# TRV_ANAREN_V0_5.net
KiCad netlist of a schematic drawn in EAGLE
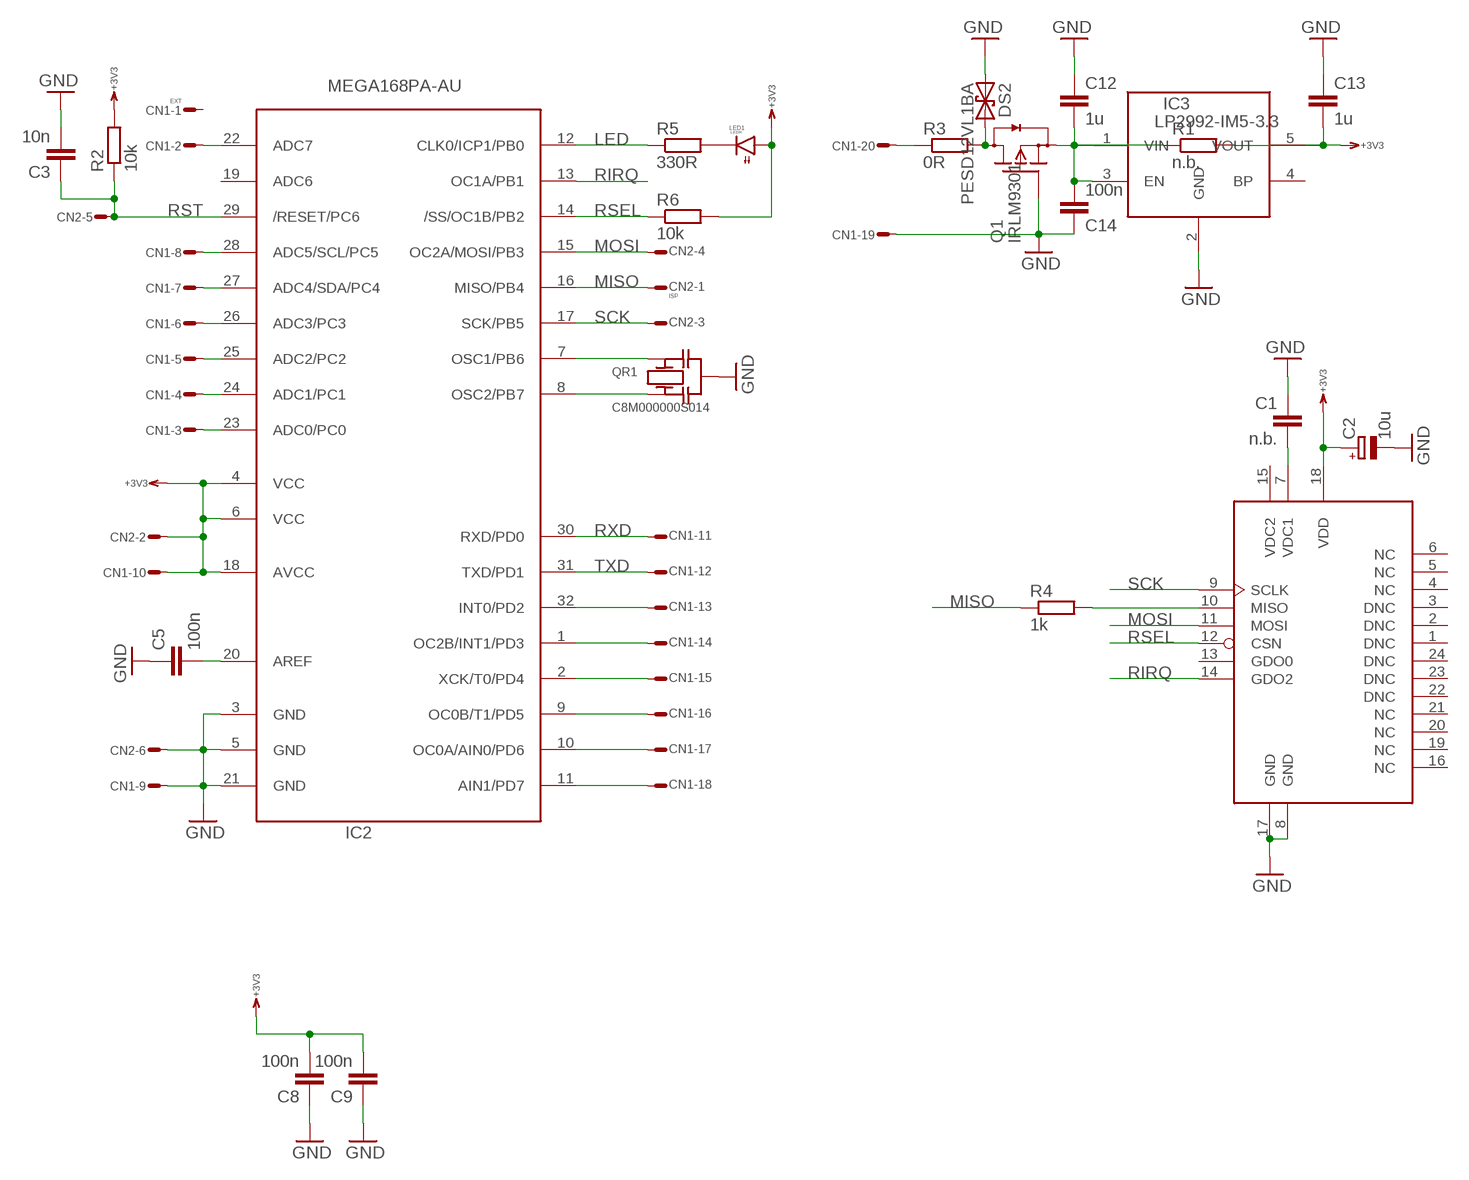
[diagram p0: schematic, sheet 1]

(export (version "E")
  (design (tool "Eeschema 10.0.6"))
  (components
    (comp (ref "C1")
      (value "n.b.")
      (footprint "eagle-import:0603")
      (libsource (lib "eagle-import") (part "C0603"))
    )
    (comp (ref "C2")
      (value "10u")
      (footprint "eagle-import:SMC_B")
      (libsource (lib "eagle-import") (part "C_POLSMCB"))
    )
    (comp (ref "C3")
      (value "10n")
      (footprint "eagle-import:0603")
      (libsource (lib "eagle-import") (part "C0603"))
    )
    (comp (ref "C5")
      (value "100n")
      (footprint "eagle-import:0603")
      (libsource (lib "eagle-import") (part "C0603"))
    )
    (comp (ref "C8")
      (value "100n")
      (footprint "eagle-import:0603")
      (libsource (lib "eagle-import") (part "C0603"))
    )
    (comp (ref "C9")
      (value "100n")
      (footprint "eagle-import:0603")
      (libsource (lib "eagle-import") (part "C0603"))
    )
    (comp (ref "C12")
      (value "1u")
      (footprint "eagle-import:0603")
      (libsource (lib "eagle-import") (part "C0603"))
    )
    (comp (ref "C13")
      (value "1u")
      (footprint "eagle-import:0603")
      (libsource (lib "eagle-import") (part "C0603"))
    )
    (comp (ref "C14")
      (value "100n")
      (footprint "eagle-import:0603")
      (libsource (lib "eagle-import") (part "C0603"))
    )
    (comp (ref "CN1")
      (value "EXT")
      (footprint "eagle-import:ML20S")
      (libsource (lib "eagle-import") (part "ML20?ES"))
    )
    (comp (ref "CN2")
      (value "ISP")
      (footprint "eagle-import:ML6S")
      (libsource (lib "eagle-import") (part "ML6ES"))
    )
    (comp (ref "DS2")
      (value "PESD12VL1BA")
      (footprint "eagle-import:SOD323")
      (libsource (lib "eagle-import") (part "TVS-U323"))
    )
    (comp (ref "IC2")
      (value "MEGA168PA-AU")
      (footprint "eagle-import:TQFP32-08")
      (libsource (lib "eagle-import") (part "MEGA168PA"))
    )
    (comp (ref "IC3")
      (value "LP2992-IM5-3.3")
      (footprint "eagle-import:SOT23-5")
      (libsource (lib "eagle-import") (part "LDO"))
    )
    (comp (ref "LED1")
      (value "LEDR")
      (footprint "eagle-import:0603")
      (libsource (lib "eagle-import") (part "LED0603"))
    )
    (comp (ref "Q1")
      (value "IRLM9301")
      (footprint "eagle-import:SOT23")
      (libsource (lib "eagle-import") (part "FET-PDSOT23"))
    )
    (comp (ref "QR1")
      (value "C8M000000S014")
      (footprint "eagle-import:CR")
      (libsource (lib "eagle-import") (part "QRCR"))
    )
    (comp (ref "R1")
      (value "n.b.")
      (footprint "eagle-import:0603")
      (libsource (lib "eagle-import") (part "R0603"))
    )
    (comp (ref "R2")
      (value "10k")
      (footprint "eagle-import:0603")
      (libsource (lib "eagle-import") (part "R0603"))
    )
    (comp (ref "R3")
      (value "0R")
      (footprint "eagle-import:0603")
      (libsource (lib "eagle-import") (part "R0603"))
    )
    (comp (ref "R4")
      (value "1k")
      (footprint "eagle-import:0603")
      (libsource (lib "eagle-import") (part "R0603"))
    )
    (comp (ref "R5")
      (value "330R")
      (footprint "eagle-import:0603")
      (libsource (lib "eagle-import") (part "R0603"))
    )
    (comp (ref "R6")
      (value "10k")
      (footprint "eagle-import:0603")
      (libsource (lib "eagle-import") (part "R0603"))
    )
    (comp (ref "RF1")
      (value "ANARENC")
      (footprint "eagle-import:ANAREN_C")
      (libsource (lib "eagle-import") (part "ANARENC"))
    )
  )
  (nets
    (net (code "1") (name "+3V3") (class "Default")
      (node (ref "C13") (pin "2") (pinfunction "2_2") (pintype "passive"))
      (node (ref "C2") (pin "+") (pinfunction "+_+") (pintype "passive"))
      (node (ref "C8") (pin "2") (pinfunction "2_2") (pintype "passive"))
      (node (ref "C9") (pin "2") (pinfunction "2_2") (pintype "passive"))
      (node (ref "CN1") (pin "10") (pinfunction "S_10") (pintype "passive"))
      (node (ref "CN2") (pin "2") (pinfunction "S_2") (pintype "passive"))
      (node (ref "IC2") (pin "18") (pinfunction "AVCC_18") (pintype "bidirectional"))
      (node (ref "IC2") (pin "4") (pinfunction "VCC_4") (pintype "bidirectional"))
      (node (ref "IC2") (pin "6") (pinfunction "VCC_6") (pintype "bidirectional"))
      (node (ref "IC3") (pin "5") (pinfunction "VOUT_5") (pintype "bidirectional"))
      (node (ref "LED1") (pin "1") (pinfunction "A_1") (pintype "bidirectional"))
      (node (ref "R1") (pin "2") (pinfunction "2_2") (pintype "passive"))
      (node (ref "R2") (pin "2") (pinfunction "2_2") (pintype "passive"))
      (node (ref "R6") (pin "2") (pinfunction "2_2") (pintype "passive"))
      (node (ref "RF1") (pin "18") (pinfunction "VDD_18") (pintype "bidirectional"))
    )
    (net (code "2") (name "/LED") (class "Default")
      (node (ref "IC2") (pin "12") (pinfunction "CLK0/ICP1/PB0_12") (pintype "bidirectional"))
      (node (ref "R5") (pin "1") (pinfunction "1_1") (pintype "passive"))
    )
    (net (code "3") (name "/MISO") (class "Default")
      (node (ref "CN2") (pin "1") (pinfunction "S_1") (pintype "passive"))
      (node (ref "IC2") (pin "16") (pinfunction "MISO/PB4_16") (pintype "bidirectional"))
      (node (ref "R4") (pin "1") (pinfunction "1_1") (pintype "passive"))
    )
    (net (code "4") (name "/MOSI") (class "Default")
      (node (ref "CN2") (pin "4") (pinfunction "S_4") (pintype "passive"))
      (node (ref "IC2") (pin "15") (pinfunction "OC2A/MOSI/PB3_15") (pintype "bidirectional"))
      (node (ref "RF1") (pin "11") (pinfunction "MOSI_11") (pintype "input"))
    )
    (net (code "5") (name "/RIRQ") (class "Default")
      (node (ref "IC2") (pin "13") (pinfunction "OC1A/PB1_13") (pintype "bidirectional"))
      (node (ref "RF1") (pin "14") (pinfunction "GDO2_14") (pintype "bidirectional"))
    )
    (net (code "6") (name "/RSEL") (class "Default")
      (node (ref "IC2") (pin "14") (pinfunction "/SS/OC1B/PB2_14") (pintype "bidirectional"))
      (node (ref "R6") (pin "1") (pinfunction "1_1") (pintype "passive"))
      (node (ref "RF1") (pin "12") (pinfunction "CSN_12") (pintype "input"))
    )
    (net (code "7") (name "/RST") (class "Default")
      (node (ref "C3") (pin "1") (pinfunction "1_1") (pintype "passive"))
      (node (ref "CN2") (pin "5") (pinfunction "S_5") (pintype "passive"))
      (node (ref "IC2") (pin "29") (pinfunction "/RESET/PC6_29") (pintype "bidirectional"))
      (node (ref "R2") (pin "1") (pinfunction "1_1") (pintype "passive"))
    )
    (net (code "8") (name "/RXD") (class "Default")
      (node (ref "CN1") (pin "11") (pinfunction "S_11") (pintype "passive"))
      (node (ref "IC2") (pin "30") (pinfunction "RXD/PD0_30") (pintype "bidirectional"))
    )
    (net (code "9") (name "/SCK") (class "Default")
      (node (ref "CN2") (pin "3") (pinfunction "S_3") (pintype "passive"))
      (node (ref "IC2") (pin "17") (pinfunction "SCK/PB5_17") (pintype "bidirectional"))
      (node (ref "RF1") (pin "9") (pinfunction "SCLK_9") (pintype "input"))
    )
    (net (code "10") (name "/TXD") (class "Default")
      (node (ref "CN1") (pin "12") (pinfunction "S_12") (pintype "passive"))
      (node (ref "IC2") (pin "31") (pinfunction "TXD/PD1_31") (pintype "bidirectional"))
    )
    (net (code "11") (name "GND") (class "Default")
      (node (ref "C1") (pin "1") (pinfunction "1_1") (pintype "passive"))
      (node (ref "C12") (pin "1") (pinfunction "1_1") (pintype "passive"))
      (node (ref "C13") (pin "1") (pinfunction "1_1") (pintype "passive"))
      (node (ref "C14") (pin "1") (pinfunction "1_1") (pintype "passive"))
      (node (ref "C2") (pin "-") (pinfunction "-_-") (pintype "passive"))
      (node (ref "C3") (pin "2") (pinfunction "2_2") (pintype "passive"))
      (node (ref "C5") (pin "1") (pinfunction "1_1") (pintype "passive"))
      (node (ref "C8") (pin "1") (pinfunction "1_1") (pintype "passive"))
      (node (ref "C9") (pin "1") (pinfunction "1_1") (pintype "passive"))
      (node (ref "CN1") (pin "19") (pinfunction "S_19") (pintype "passive"))
      (node (ref "CN1") (pin "9") (pinfunction "S_9") (pintype "passive"))
      (node (ref "CN2") (pin "6") (pinfunction "S_6") (pintype "passive"))
      (node (ref "DS2") (pin "A") (pinfunction "1_A") (pintype "passive"))
      (node (ref "IC2") (pin "21") (pinfunction "GND_21") (pintype "bidirectional"))
      (node (ref "IC2") (pin "3") (pinfunction "GND_3") (pintype "bidirectional"))
      (node (ref "IC2") (pin "5") (pinfunction "GND_5") (pintype "bidirectional"))
      (node (ref "IC3") (pin "2") (pinfunction "GND_2") (pintype "bidirectional"))
      (node (ref "Q1") (pin "1") (pinfunction "G_1") (pintype "passive"))
      (node (ref "QR1") (pin "M") (pinfunction "M_M") (pintype "passive"))
      (node (ref "RF1") (pin "17") (pinfunction "GND_17") (pintype "bidirectional"))
      (node (ref "RF1") (pin "8") (pinfunction "GND_8") (pintype "bidirectional"))
    )
    (net (code "12") (name "Net-(CN1E-S)") (class "Default")
      (node (ref "CN1") (pin "13") (pinfunction "S_13") (pintype "passive"))
      (node (ref "IC2") (pin "32") (pinfunction "INT0/PD2_32") (pintype "bidirectional"))
    )
    (net (code "13") (name "Net-(CN1F-S)") (class "Default")
      (node (ref "CN1") (pin "14") (pinfunction "S_14") (pintype "passive"))
      (node (ref "IC2") (pin "1") (pinfunction "OC2B/INT1/PD3_1") (pintype "bidirectional"))
    )
    (net (code "14") (name "Net-(CN1G-S)") (class "Default")
      (node (ref "CN1") (pin "15") (pinfunction "S_15") (pintype "passive"))
      (node (ref "IC2") (pin "2") (pinfunction "XCK/T0/PD4_2") (pintype "bidirectional"))
    )
    (net (code "15") (name "Net-(CN1H-S)") (class "Default")
      (node (ref "CN1") (pin "16") (pinfunction "S_16") (pintype "passive"))
      (node (ref "IC2") (pin "9") (pinfunction "OC0B/T1/PD5_9") (pintype "bidirectional"))
    )
    (net (code "16") (name "Net-(CN1I-S)") (class "Default")
      (node (ref "CN1") (pin "17") (pinfunction "S_17") (pintype "passive"))
      (node (ref "IC2") (pin "10") (pinfunction "OC0A/AIN0/PD6_10") (pintype "bidirectional"))
    )
    (net (code "17") (name "Net-(CN1J-S)") (class "Default")
      (node (ref "CN1") (pin "18") (pinfunction "S_18") (pintype "passive"))
      (node (ref "IC2") (pin "11") (pinfunction "AIN1/PD7_11") (pintype "bidirectional"))
    )
    (net (code "18") (name "Net-(CN1L-S)") (class "Default")
      (node (ref "CN1") (pin "2") (pinfunction "S_2") (pintype "passive"))
      (node (ref "IC2") (pin "22") (pinfunction "ADC7_22") (pintype "bidirectional"))
    )
    (net (code "19") (name "Net-(CN1M-S)") (class "Default")
      (node (ref "CN1") (pin "20") (pinfunction "S_20") (pintype "passive"))
      (node (ref "R3") (pin "1") (pinfunction "1_1") (pintype "passive"))
    )
    (net (code "20") (name "Net-(CN1N-S)") (class "Default")
      (node (ref "CN1") (pin "3") (pinfunction "S_3") (pintype "passive"))
      (node (ref "IC2") (pin "23") (pinfunction "ADC0/PC0_23") (pintype "bidirectional"))
    )
    (net (code "21") (name "Net-(CN1O-S)") (class "Default")
      (node (ref "CN1") (pin "4") (pinfunction "S_4") (pintype "passive"))
      (node (ref "IC2") (pin "24") (pinfunction "ADC1/PC1_24") (pintype "bidirectional"))
    )
    (net (code "22") (name "Net-(CN1P-S)") (class "Default")
      (node (ref "CN1") (pin "5") (pinfunction "S_5") (pintype "passive"))
      (node (ref "IC2") (pin "25") (pinfunction "ADC2/PC2_25") (pintype "bidirectional"))
    )
    (net (code "23") (name "Net-(CN1Q-S)") (class "Default")
      (node (ref "CN1") (pin "6") (pinfunction "S_6") (pintype "passive"))
      (node (ref "IC2") (pin "26") (pinfunction "ADC3/PC3_26") (pintype "bidirectional"))
    )
    (net (code "24") (name "Net-(CN1R-S)") (class "Default")
      (node (ref "CN1") (pin "7") (pinfunction "S_7") (pintype "passive"))
      (node (ref "IC2") (pin "27") (pinfunction "ADC4/SDA/PC4_27") (pintype "bidirectional"))
    )
    (net (code "25") (name "Net-(CN1S-S)") (class "Default")
      (node (ref "CN1") (pin "8") (pinfunction "S_8") (pintype "passive"))
      (node (ref "IC2") (pin "28") (pinfunction "ADC5/SCL/PC5_28") (pintype "bidirectional"))
    )
    (net (code "26") (name "Net-(DS2-2)") (class "Default")
      (node (ref "DS2") (pin "C") (pinfunction "2_C") (pintype "passive"))
      (node (ref "Q1") (pin "3") (pinfunction "D_3") (pintype "passive"))
      (node (ref "R3") (pin "2") (pinfunction "2_2") (pintype "passive"))
    )
    (net (code "27") (name "Net-(IC2-AREF)") (class "Default")
      (node (ref "C5") (pin "2") (pinfunction "2_2") (pintype "passive"))
      (node (ref "IC2") (pin "20") (pinfunction "AREF_20") (pintype "bidirectional"))
    )
    (net (code "28") (name "Net-(IC2-OSC1{slash}PB6)") (class "Default")
      (node (ref "IC2") (pin "7") (pinfunction "OSC1/PB6_7") (pintype "bidirectional"))
      (node (ref "QR1") (pin "2") (pinfunction "2_2") (pintype "passive"))
    )
    (net (code "29") (name "Net-(IC2-OSC2{slash}PB7)") (class "Default")
      (node (ref "IC2") (pin "8") (pinfunction "OSC2/PB7_8") (pintype "bidirectional"))
      (node (ref "QR1") (pin "1") (pinfunction "1_1") (pintype "passive"))
    )
    (net (code "30") (name "Net-(IC3-EN)") (class "Default")
      (node (ref "C12") (pin "2") (pinfunction "2_2") (pintype "passive"))
      (node (ref "C14") (pin "2") (pinfunction "2_2") (pintype "passive"))
      (node (ref "IC3") (pin "1") (pinfunction "VIN_1") (pintype "bidirectional"))
      (node (ref "IC3") (pin "3") (pinfunction "EN_3") (pintype "bidirectional"))
      (node (ref "Q1") (pin "2") (pinfunction "S_2") (pintype "passive"))
      (node (ref "R1") (pin "1") (pinfunction "1_1") (pintype "passive"))
    )
    (net (code "31") (name "Net-(LED1-C)") (class "Default")
      (node (ref "LED1") (pin "2") (pinfunction "C_2") (pintype "bidirectional"))
      (node (ref "R5") (pin "2") (pinfunction "2_2") (pintype "passive"))
    )
    (net (code "32") (name "Net-(RF1-MISO)") (class "Default")
      (node (ref "R4") (pin "2") (pinfunction "2_2") (pintype "passive"))
      (node (ref "RF1") (pin "10") (pinfunction "MISO_10") (pintype "output"))
    )
    (net (code "33") (name "Net-(RF1-VDC1)") (class "Default")
      (node (ref "C1") (pin "2") (pinfunction "2_2") (pintype "passive"))
      (node (ref "RF1") (pin "7") (pinfunction "VDC1_7") (pintype "bidirectional"))
    )
    (net (code "34") (name "unconnected-(CN1A-S-Pad1)") (class "Default")
      (node (ref "CN1") (pin "1") (pinfunction "S_1") (pintype "passive"))
    )
    (net (code "35") (name "unconnected-(IC2-ADC6-Pad19)") (class "Default")
      (node (ref "IC2") (pin "19") (pinfunction "ADC6_19") (pintype "bidirectional"))
    )
    (net (code "36") (name "unconnected-(IC3-BP-Pad4)") (class "Default")
      (node (ref "IC3") (pin "4") (pinfunction "BP_4") (pintype "bidirectional"))
    )
    (net (code "37") (name "unconnected-(RF1-DNC-Pad1)") (class "Default")
      (node (ref "RF1") (pin "1") (pinfunction "DNC_1") (pintype "bidirectional"))
    )
    (net (code "38") (name "unconnected-(RF1-DNC-Pad2)") (class "Default")
      (node (ref "RF1") (pin "2") (pinfunction "DNC_2") (pintype "bidirectional"))
    )
    (net (code "39") (name "unconnected-(RF1-DNC-Pad3)") (class "Default")
      (node (ref "RF1") (pin "3") (pinfunction "DNC_3") (pintype "bidirectional"))
    )
    (net (code "40") (name "unconnected-(RF1-DNC-Pad22)") (class "Default")
      (node (ref "RF1") (pin "22") (pinfunction "DNC_22") (pintype "bidirectional"))
    )
    (net (code "41") (name "unconnected-(RF1-DNC-Pad23)") (class "Default")
      (node (ref "RF1") (pin "23") (pinfunction "DNC_23") (pintype "bidirectional"))
    )
    (net (code "42") (name "unconnected-(RF1-DNC-Pad24)") (class "Default")
      (node (ref "RF1") (pin "24") (pinfunction "DNC_24") (pintype "bidirectional"))
    )
    (net (code "43") (name "unconnected-(RF1-GDO0-Pad13)") (class "Default")
      (node (ref "RF1") (pin "13") (pinfunction "GDO0_13") (pintype "bidirectional"))
    )
    (net (code "44") (name "unconnected-(RF1-NC-Pad4)") (class "Default")
      (node (ref "RF1") (pin "4") (pinfunction "NC_4") (pintype "bidirectional"))
    )
    (net (code "45") (name "unconnected-(RF1-NC-Pad5)") (class "Default")
      (node (ref "RF1") (pin "5") (pinfunction "NC_5") (pintype "bidirectional"))
    )
    (net (code "46") (name "unconnected-(RF1-NC-Pad6)") (class "Default")
      (node (ref "RF1") (pin "6") (pinfunction "NC_6") (pintype "bidirectional"))
    )
    (net (code "47") (name "unconnected-(RF1-NC-Pad16)") (class "Default")
      (node (ref "RF1") (pin "16") (pinfunction "NC_16") (pintype "bidirectional"))
    )
    (net (code "48") (name "unconnected-(RF1-NC-Pad19)") (class "Default")
      (node (ref "RF1") (pin "19") (pinfunction "NC_19") (pintype "bidirectional"))
    )
    (net (code "49") (name "unconnected-(RF1-NC-Pad20)") (class "Default")
      (node (ref "RF1") (pin "20") (pinfunction "NC_20") (pintype "bidirectional"))
    )
    (net (code "50") (name "unconnected-(RF1-NC-Pad21)") (class "Default")
      (node (ref "RF1") (pin "21") (pinfunction "NC_21") (pintype "bidirectional"))
    )
    (net (code "51") (name "unconnected-(RF1-VDC2-Pad15)") (class "Default")
      (node (ref "RF1") (pin "15") (pinfunction "VDC2_15") (pintype "bidirectional"))
    )
  )
)
